# Connector.net
KiCad netlist of a schematic drawn in Altium Designer
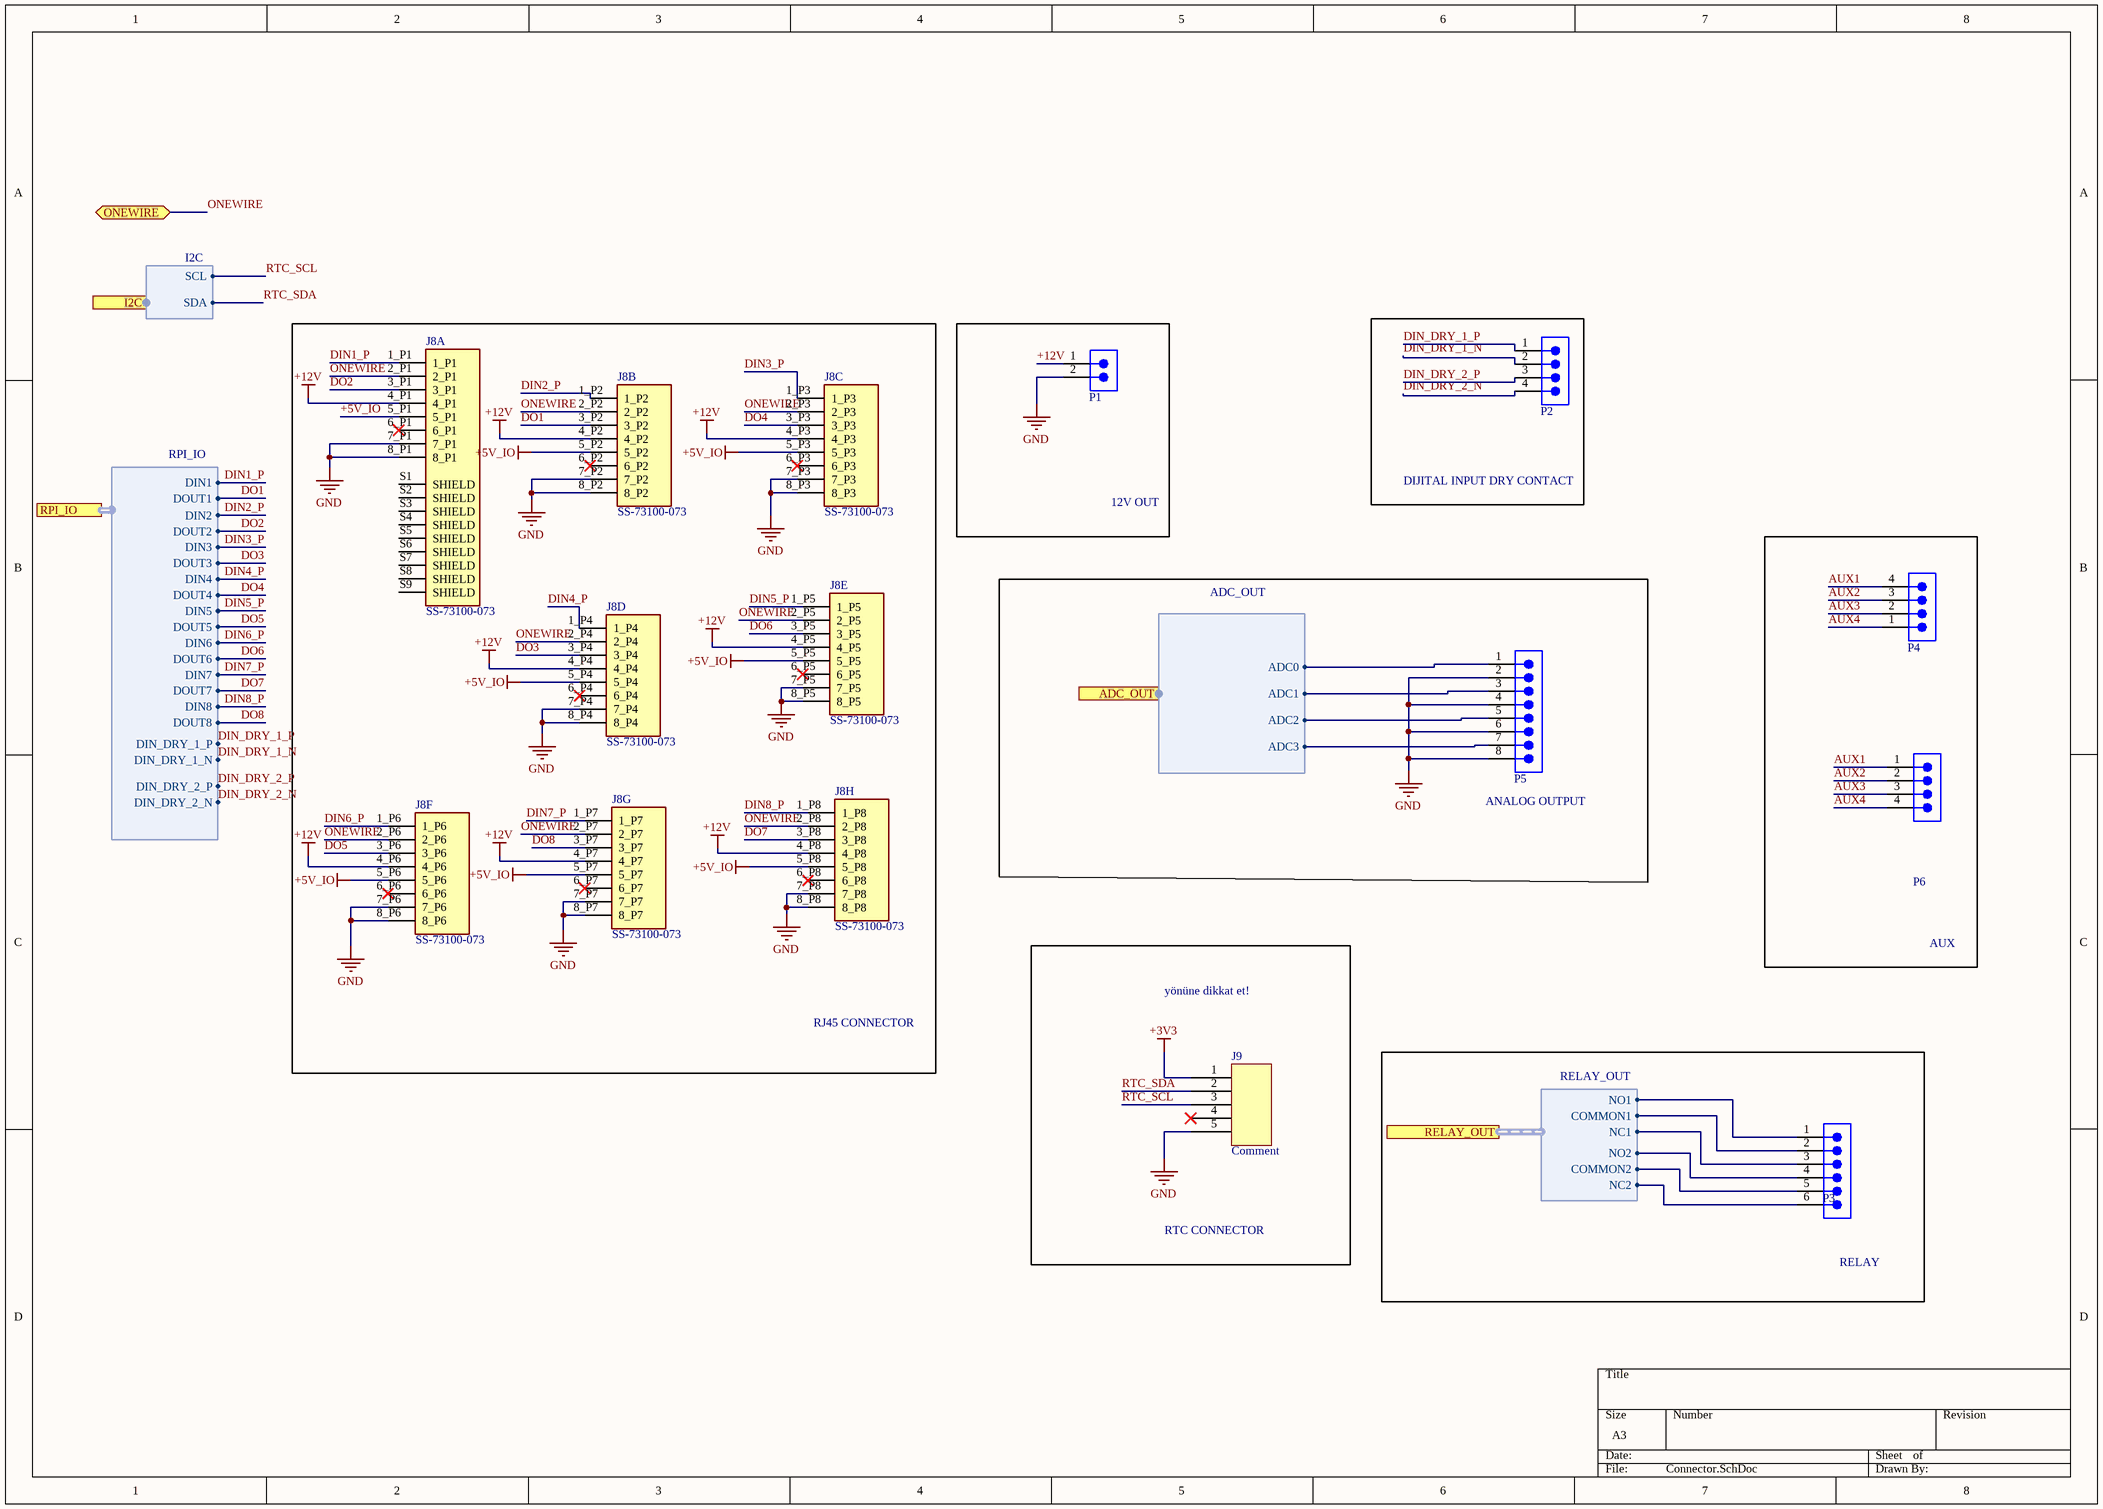
[diagram p0: Connector.SchDoc]

(export (version "E")
  (design (tool "Eeschema 10.0.6"))
  (components
    (comp (ref "J8")
      (value "SS-73100-073")
      (footprint "BEL_SS-73100-073")
      (description "Jack Modular Connector RJ45, Ethernet RA")
      (fields
        (field (name "DIGI-KEY_PART_NUMBER") "SS-73100-073F-ND")
        (field (name "MF") "Stewart Connector")
      )
      (libsource (lib "anayurt") (part "SS-73100-073"))
    )
    (comp (ref "J9")
      (value "Comment")
      (footprint "2.54_5P")
      (description "2.54_5P_HDR")
      (libsource (lib "anayurt") (part "2.54_5P_HDR"))
    )
    (comp (ref "P1")
      (value "691322310002")
      (footprint "691322310002")
      (description "WR-TBL Series 322 - 3.81 mm Horizontal 2 pin")
      (fields (field (name "MANUFACTURER") "Wurth Elektronik"))
      (libsource (lib "anayurt") (part "691322310002"))
    )
    (comp (ref "P2")
      (value "691322310004")
      (footprint "691322310004")
      (description "WR-TBL Series 322 - 3.81 mm Horizontal")
      (fields (field (name "MANUFACTURER") "Wurth Elektronik"))
      (libsource (lib "anayurt") (part "691322310004"))
    )
    (comp (ref "P3")
      (value "691305540006")
      (footprint "691305540006")
      (description "WR-TBL Series 3055 - 5.08 mm 6 pin")
      (fields (field (name "MANUFACTURER") "Wurth Elektronik"))
      (libsource (lib "anayurt") (part "691305540006"))
    )
    (comp (ref "P4")
      (value "691322310004")
      (footprint "691322310004")
      (description "WR-TBL Series 322 - 3.81 mm Horizontal")
      (fields (field (name "MANUFACTURER") "Wurth Elektronik"))
      (libsource (lib "anayurt") (part "691322310004"))
    )
    (comp (ref "P5")
      (value "691322310008")
      (footprint "691322310008")
      (description "WR-TBL Series 322 - 3.81 mm Horizontal 8 pin")
      (fields (field (name "MANUFACTURER") "Wurth Elektronik"))
      (libsource (lib "anayurt") (part "691322310008"))
    )
    (comp (ref "P6")
      (value "691322310004")
      (footprint "691322310004")
      (description "WR-TBL Series 322 - 3.81 mm Horizontal")
      (fields (field (name "MANUFACTURER") "Wurth Elektronik"))
      (libsource (lib "anayurt") (part "691322310004"))
    )
  )
  (nets
    (net (code "5") (name "+3V3") (class "Default")
      (node (ref "J9") (pin "1") (pinfunction "1_1") (pintype "passive"))
    )
    (net (code "6") (name "+5V_IO") (class "Default")
      (node (ref "J8") (pin "5_P1") (pinfunction "5_P1_5_P1") (pintype "passive"))
      (node (ref "J8") (pin "5_P2") (pinfunction "5_P2_5_P2") (pintype "passive"))
      (node (ref "J8") (pin "5_P3") (pinfunction "5_P3_5_P3") (pintype "passive"))
      (node (ref "J8") (pin "5_P4") (pinfunction "5_P4_5_P4") (pintype "passive"))
      (node (ref "J8") (pin "5_P5") (pinfunction "5_P5_5_P5") (pintype "passive"))
      (node (ref "J8") (pin "5_P6") (pinfunction "5_P6_5_P6") (pintype "passive"))
      (node (ref "J8") (pin "5_P7") (pinfunction "5_P7_5_P7") (pintype "passive"))
      (node (ref "J8") (pin "5_P8") (pinfunction "5_P8_5_P8") (pintype "passive"))
    )
    (net (code "7") (name "+12V") (class "Default")
      (node (ref "J8") (pin "4_P1") (pinfunction "4_P1_4_P1") (pintype "passive"))
      (node (ref "J8") (pin "4_P2") (pinfunction "4_P2_4_P2") (pintype "passive"))
      (node (ref "J8") (pin "4_P3") (pinfunction "4_P3_4_P3") (pintype "passive"))
      (node (ref "J8") (pin "4_P4") (pinfunction "4_P4_4_P4") (pintype "passive"))
      (node (ref "J8") (pin "4_P5") (pinfunction "4_P5_4_P5") (pintype "passive"))
      (node (ref "J8") (pin "4_P6") (pinfunction "4_P6_4_P6") (pintype "passive"))
      (node (ref "J8") (pin "4_P7") (pinfunction "4_P7_4_P7") (pintype "passive"))
      (node (ref "J8") (pin "4_P8") (pinfunction "4_P8_4_P8") (pintype "passive"))
      (node (ref "P1") (pin "1") (pinfunction "1_1") (pintype "passive"))
    )
    (net (code "8") (name "/ADC0") (class "Default")
      (node (ref "P5") (pin "1") (pinfunction "1_1") (pintype "passive"))
    )
    (net (code "9") (name "/ADC1") (class "Default")
      (node (ref "P5") (pin "3") (pinfunction "3_3") (pintype "passive"))
    )
    (net (code "10") (name "/ADC2") (class "Default")
      (node (ref "P5") (pin "5") (pinfunction "5_5") (pintype "passive"))
    )
    (net (code "11") (name "/ADC3") (class "Default")
      (node (ref "P5") (pin "7") (pinfunction "7_7") (pintype "passive"))
    )
    (net (code "12") (name "/AUX1") (class "Default")
      (node (ref "P4") (pin "4") (pinfunction "4_4") (pintype "passive"))
      (node (ref "P6") (pin "1") (pinfunction "1_1") (pintype "passive"))
    )
    (net (code "13") (name "/AUX2") (class "Default")
      (node (ref "P4") (pin "3") (pinfunction "3_3") (pintype "passive"))
      (node (ref "P6") (pin "2") (pinfunction "2_2") (pintype "passive"))
    )
    (net (code "14") (name "/AUX3") (class "Default")
      (node (ref "P4") (pin "2") (pinfunction "2_2") (pintype "passive"))
      (node (ref "P6") (pin "3") (pinfunction "3_3") (pintype "passive"))
    )
    (net (code "15") (name "/AUX4") (class "Default")
      (node (ref "P4") (pin "1") (pinfunction "1_1") (pintype "passive"))
      (node (ref "P6") (pin "4") (pinfunction "4_4") (pintype "passive"))
    )
    (net (code "16") (name "/COMMON1") (class "Default")
      (node (ref "P3") (pin "2") (pinfunction "2_2") (pintype "passive"))
    )
    (net (code "17") (name "/COMMON2") (class "Default")
      (node (ref "P3") (pin "5") (pinfunction "5_5") (pintype "passive"))
    )
    (net (code "18") (name "/DIN1_P") (class "Default")
      (node (ref "J8") (pin "1_P1") (pinfunction "1_P1_1_P1") (pintype "passive"))
    )
    (net (code "19") (name "/DIN2_P") (class "Default")
      (node (ref "J8") (pin "1_P2") (pinfunction "1_P2_1_P2") (pintype "passive"))
    )
    (net (code "20") (name "/DIN3_P") (class "Default")
      (node (ref "J8") (pin "1_P3") (pinfunction "1_P3_1_P3") (pintype "passive"))
    )
    (net (code "21") (name "/DIN4_P") (class "Default")
      (node (ref "J8") (pin "1_P4") (pinfunction "1_P4_1_P4") (pintype "passive"))
    )
    (net (code "22") (name "/DIN5_P") (class "Default")
      (node (ref "J8") (pin "1_P5") (pinfunction "1_P5_1_P5") (pintype "passive"))
    )
    (net (code "23") (name "/DIN6_P") (class "Default")
      (node (ref "J8") (pin "1_P6") (pinfunction "1_P6_1_P6") (pintype "passive"))
    )
    (net (code "24") (name "/DIN7_P") (class "Default")
      (node (ref "J8") (pin "1_P7") (pinfunction "1_P7_1_P7") (pintype "passive"))
    )
    (net (code "25") (name "/DIN8_P") (class "Default")
      (node (ref "J8") (pin "1_P8") (pinfunction "1_P8_1_P8") (pintype "passive"))
    )
    (net (code "26") (name "/DIN_DRY_1_N") (class "Default")
      (node (ref "P2") (pin "2") (pinfunction "2_2") (pintype "passive"))
    )
    (net (code "27") (name "/DIN_DRY_1_P") (class "Default")
      (node (ref "P2") (pin "1") (pinfunction "1_1") (pintype "passive"))
    )
    (net (code "28") (name "/DIN_DRY_2_N") (class "Default")
      (node (ref "P2") (pin "4") (pinfunction "4_4") (pintype "passive"))
    )
    (net (code "29") (name "/DIN_DRY_2_P") (class "Default")
      (node (ref "P2") (pin "3") (pinfunction "3_3") (pintype "passive"))
    )
    (net (code "30") (name "/DO1") (class "Default")
      (node (ref "J8") (pin "3_P2") (pinfunction "3_P2_3_P2") (pintype "passive"))
    )
    (net (code "31") (name "/DO2") (class "Default")
      (node (ref "J8") (pin "3_P1") (pinfunction "3_P1_3_P1") (pintype "passive"))
    )
    (net (code "32") (name "/DO3") (class "Default")
      (node (ref "J8") (pin "3_P4") (pinfunction "3_P4_3_P4") (pintype "passive"))
    )
    (net (code "33") (name "/DO4") (class "Default")
      (node (ref "J8") (pin "3_P3") (pinfunction "3_P3_3_P3") (pintype "passive"))
    )
    (net (code "34") (name "/DO5") (class "Default")
      (node (ref "J8") (pin "3_P6") (pinfunction "3_P6_3_P6") (pintype "passive"))
    )
    (net (code "35") (name "/DO6") (class "Default")
      (node (ref "J8") (pin "3_P5") (pinfunction "3_P5_3_P5") (pintype "passive"))
    )
    (net (code "36") (name "/DO7") (class "Default")
      (node (ref "J8") (pin "3_P8") (pinfunction "3_P8_3_P8") (pintype "passive"))
    )
    (net (code "37") (name "/DO8") (class "Default")
      (node (ref "J8") (pin "3_P7") (pinfunction "3_P7_3_P7") (pintype "passive"))
    )
    (net (code "38") (name "/NC1") (class "Default")
      (node (ref "P3") (pin "3") (pinfunction "3_3") (pintype "passive"))
    )
    (net (code "39") (name "/NC2") (class "Default")
      (node (ref "P3") (pin "6") (pinfunction "6_6") (pintype "passive"))
    )
    (net (code "40") (name "/NO1") (class "Default")
      (node (ref "P3") (pin "1") (pinfunction "1_1") (pintype "passive"))
    )
    (net (code "41") (name "/NO2") (class "Default")
      (node (ref "P3") (pin "4") (pinfunction "4_4") (pintype "passive"))
    )
    (net (code "42") (name "/ONEWIRE") (class "Default")
      (node (ref "J8") (pin "2_P1") (pinfunction "2_P1_2_P1") (pintype "passive"))
      (node (ref "J8") (pin "2_P2") (pinfunction "2_P2_2_P2") (pintype "passive"))
      (node (ref "J8") (pin "2_P3") (pinfunction "2_P3_2_P3") (pintype "passive"))
      (node (ref "J8") (pin "2_P4") (pinfunction "2_P4_2_P4") (pintype "passive"))
      (node (ref "J8") (pin "2_P5") (pinfunction "2_P5_2_P5") (pintype "passive"))
      (node (ref "J8") (pin "2_P6") (pinfunction "2_P6_2_P6") (pintype "passive"))
      (node (ref "J8") (pin "2_P7") (pinfunction "2_P7_2_P7") (pintype "passive"))
      (node (ref "J8") (pin "2_P8") (pinfunction "2_P8_2_P8") (pintype "passive"))
    )
    (net (code "43") (name "/RTC_SCL") (class "Default")
      (node (ref "J9") (pin "3") (pinfunction "3_3") (pintype "passive"))
    )
    (net (code "44") (name "/RTC_SDA") (class "Default")
      (node (ref "J9") (pin "2") (pinfunction "2_2") (pintype "passive"))
    )
    (net (code "49") (name "GND") (class "Default")
      (node (ref "J8") (pin "7_P1") (pinfunction "7_P1_7_P1") (pintype "passive"))
      (node (ref "J8") (pin "7_P2") (pinfunction "7_P2_7_P2") (pintype "passive"))
      (node (ref "J8") (pin "7_P3") (pinfunction "7_P3_7_P3") (pintype "passive"))
      (node (ref "J8") (pin "7_P4") (pinfunction "7_P4_7_P4") (pintype "passive"))
      (node (ref "J8") (pin "7_P5") (pinfunction "7_P5_7_P5") (pintype "passive"))
      (node (ref "J8") (pin "7_P6") (pinfunction "7_P6_7_P6") (pintype "passive"))
      (node (ref "J8") (pin "7_P7") (pinfunction "7_P7_7_P7") (pintype "passive"))
      (node (ref "J8") (pin "7_P8") (pinfunction "7_P8_7_P8") (pintype "passive"))
      (node (ref "J8") (pin "8_P1") (pinfunction "8_P1_8_P1") (pintype "passive"))
      (node (ref "J8") (pin "8_P2") (pinfunction "8_P2_8_P2") (pintype "passive"))
      (node (ref "J8") (pin "8_P3") (pinfunction "8_P3_8_P3") (pintype "passive"))
      (node (ref "J8") (pin "8_P4") (pinfunction "8_P4_8_P4") (pintype "passive"))
      (node (ref "J8") (pin "8_P5") (pinfunction "8_P5_8_P5") (pintype "passive"))
      (node (ref "J8") (pin "8_P6") (pinfunction "8_P6_8_P6") (pintype "passive"))
      (node (ref "J8") (pin "8_P7") (pinfunction "8_P7_8_P7") (pintype "passive"))
      (node (ref "J8") (pin "8_P8") (pinfunction "8_P8_8_P8") (pintype "passive"))
      (node (ref "J9") (pin "5") (pinfunction "5_5") (pintype "passive"))
      (node (ref "P1") (pin "2") (pinfunction "2_2") (pintype "passive"))
      (node (ref "P5") (pin "2") (pinfunction "2_2") (pintype "passive"))
      (node (ref "P5") (pin "4") (pinfunction "4_4") (pintype "passive"))
      (node (ref "P5") (pin "6") (pinfunction "6_6") (pintype "passive"))
      (node (ref "P5") (pin "8") (pinfunction "8_8") (pintype "passive"))
    )
    (net (code "50") (name "unconnected-(J8-Pad6_P1)") (class "Default")
      (node (ref "J8") (pin "6_P1") (pinfunction "6_P1_6_P1") (pintype "passive+no_connect"))
    )
    (net (code "51") (name "unconnected-(J8-Pad6_P2)") (class "Default")
      (node (ref "J8") (pin "6_P2") (pinfunction "6_P2_6_P2") (pintype "passive+no_connect"))
    )
    (net (code "52") (name "unconnected-(J8-Pad6_P3)") (class "Default")
      (node (ref "J8") (pin "6_P3") (pinfunction "6_P3_6_P3") (pintype "passive+no_connect"))
    )
    (net (code "53") (name "unconnected-(J8-Pad6_P4)") (class "Default")
      (node (ref "J8") (pin "6_P4") (pinfunction "6_P4_6_P4") (pintype "passive+no_connect"))
    )
    (net (code "54") (name "unconnected-(J8-Pad6_P5)") (class "Default")
      (node (ref "J8") (pin "6_P5") (pinfunction "6_P5_6_P5") (pintype "passive+no_connect"))
    )
    (net (code "55") (name "unconnected-(J8-Pad6_P6)") (class "Default")
      (node (ref "J8") (pin "6_P6") (pinfunction "6_P6_6_P6") (pintype "passive+no_connect"))
    )
    (net (code "56") (name "unconnected-(J8-Pad6_P7)") (class "Default")
      (node (ref "J8") (pin "6_P7") (pinfunction "6_P7_6_P7") (pintype "passive+no_connect"))
    )
    (net (code "57") (name "unconnected-(J8-Pad6_P8)") (class "Default")
      (node (ref "J8") (pin "6_P8") (pinfunction "6_P8_6_P8") (pintype "passive+no_connect"))
    )
    (net (code "58") (name "unconnected-(J8A-SHIELD-PadS1)") (class "Default")
      (node (ref "J8") (pin "S1") (pinfunction "SHIELD_S1") (pintype "passive"))
    )
    (net (code "59") (name "unconnected-(J8A-SHIELD-PadS2)") (class "Default")
      (node (ref "J8") (pin "S2") (pinfunction "SHIELD_S2") (pintype "passive"))
    )
    (net (code "60") (name "unconnected-(J8A-SHIELD-PadS3)") (class "Default")
      (node (ref "J8") (pin "S3") (pinfunction "SHIELD_S3") (pintype "passive"))
    )
    (net (code "61") (name "unconnected-(J8A-SHIELD-PadS4)") (class "Default")
      (node (ref "J8") (pin "S4") (pinfunction "SHIELD_S4") (pintype "passive"))
    )
    (net (code "62") (name "unconnected-(J8A-SHIELD-PadS5)") (class "Default")
      (node (ref "J8") (pin "S5") (pinfunction "SHIELD_S5") (pintype "passive"))
    )
    (net (code "63") (name "unconnected-(J8A-SHIELD-PadS6)") (class "Default")
      (node (ref "J8") (pin "S6") (pinfunction "SHIELD_S6") (pintype "passive"))
    )
    (net (code "64") (name "unconnected-(J8A-SHIELD-PadS7)") (class "Default")
      (node (ref "J8") (pin "S7") (pinfunction "SHIELD_S7") (pintype "passive"))
    )
    (net (code "65") (name "unconnected-(J8A-SHIELD-PadS8)") (class "Default")
      (node (ref "J8") (pin "S8") (pinfunction "SHIELD_S8") (pintype "passive"))
    )
    (net (code "66") (name "unconnected-(J8A-SHIELD-PadS9)") (class "Default")
      (node (ref "J8") (pin "S9") (pinfunction "SHIELD_S9") (pintype "passive"))
    )
    (net (code "67") (name "unconnected-(J9-Pad4)") (class "Default")
      (node (ref "J9") (pin "4") (pinfunction "4_4") (pintype "passive+no_connect"))
    )
  )
)
